# working.net
KiCad netlist of a schematic drawn in EAGLE
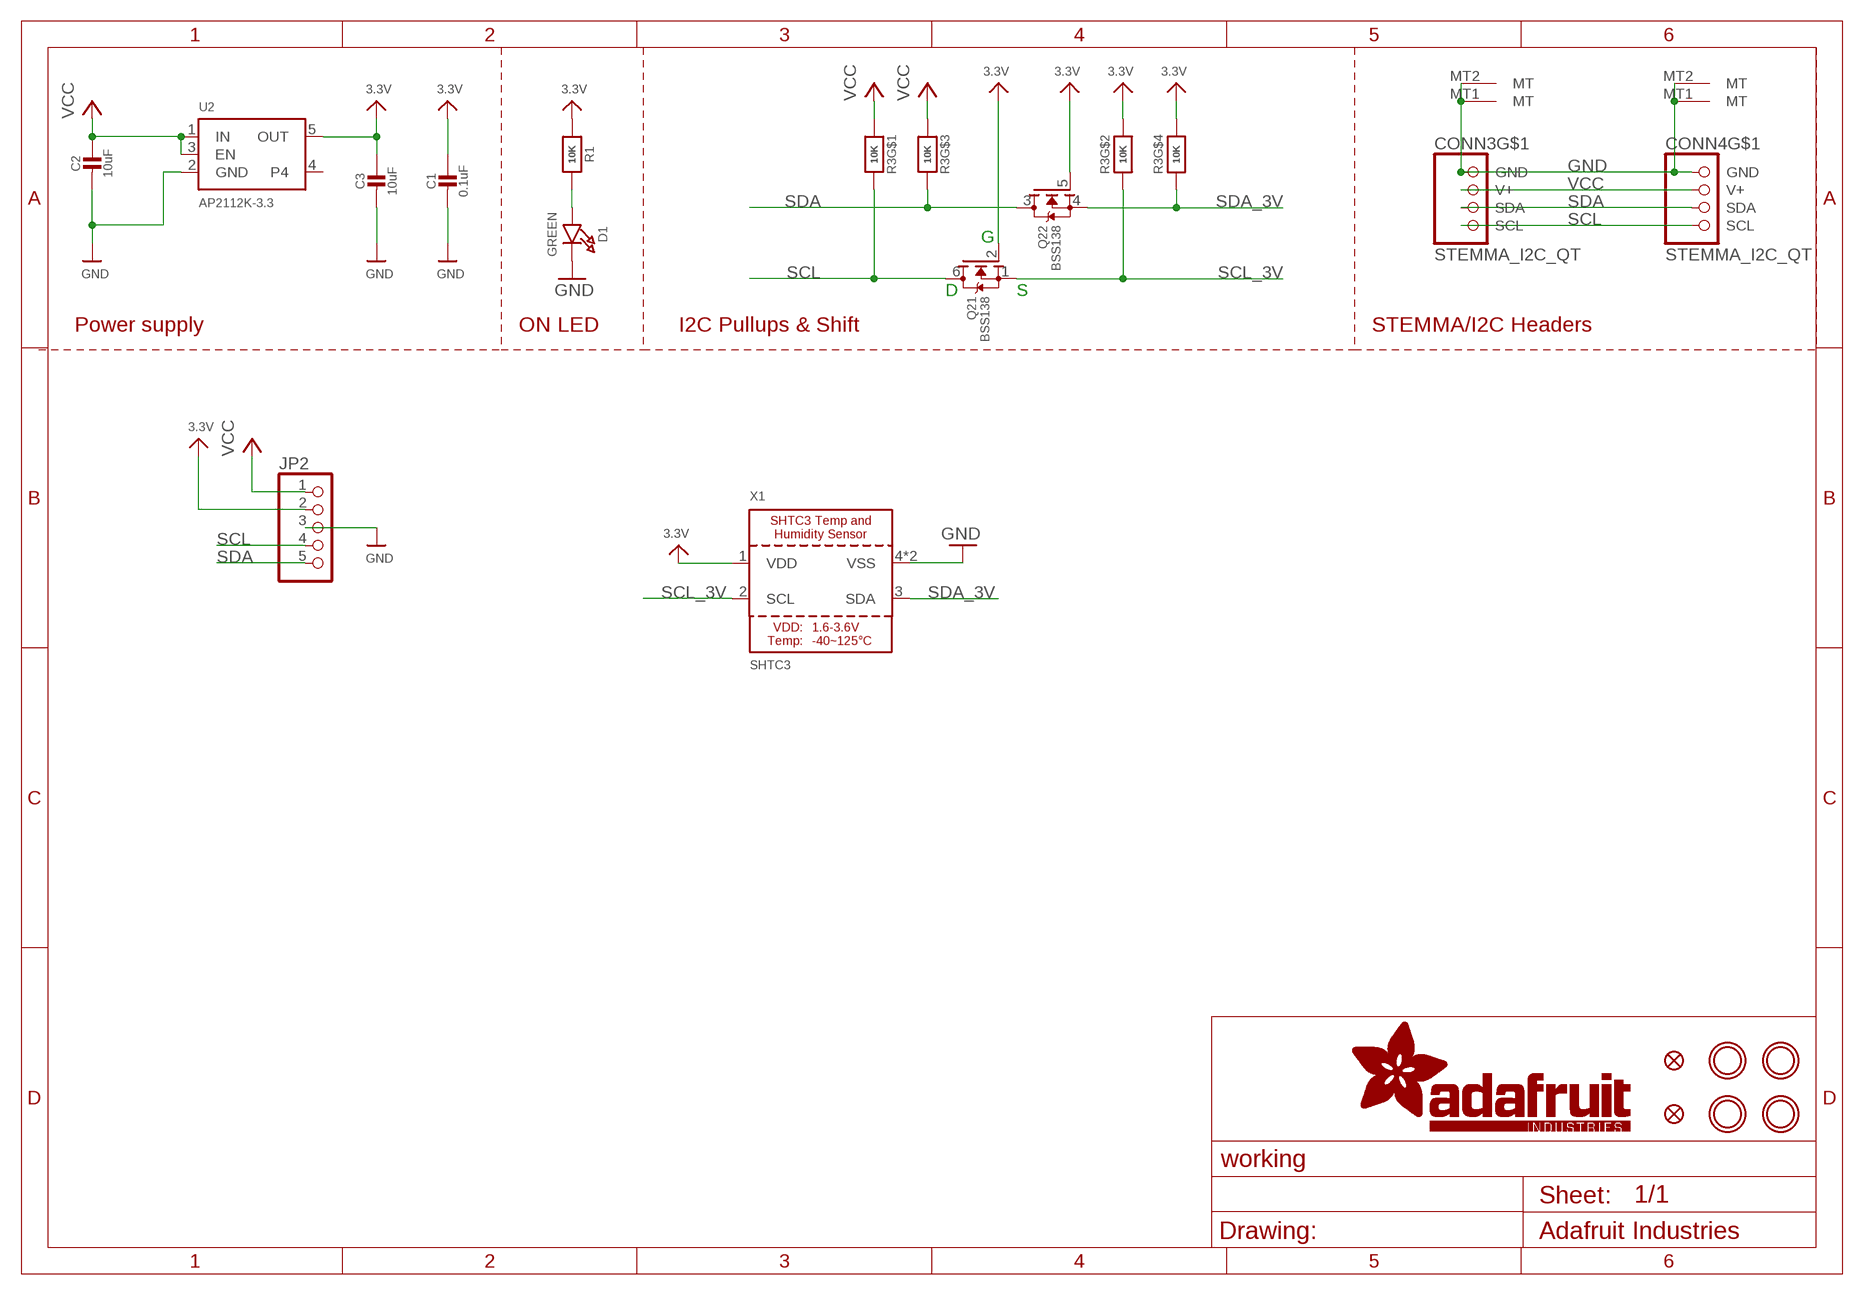
[diagram p0: schematic, sheet 1]

(export (version "E")
  (design (tool "Eeschema 10.0.6"))
  (components
    (comp (ref "C1")
      (value "0.1uF")
      (footprint "eagle-import:0603-NO")
      (libsource (lib "eagle-import") (part "CAP_CERAMIC0603_NO"))
    )
    (comp (ref "C2")
      (value "10uF")
      (footprint "eagle-import:0805-NO")
      (libsource (lib "eagle-import") (part "CAP_CERAMIC0805-NOOUTLINE"))
    )
    (comp (ref "C3")
      (value "10uF")
      (footprint "eagle-import:0805-NO")
      (libsource (lib "eagle-import") (part "CAP_CERAMIC0805-NOOUTLINE"))
    )
    (comp (ref "CONN3")
      (value "STEMMA_I2C_QT")
      (footprint "eagle-import:JST_SH4")
      (libsource (lib "eagle-import") (part "STEMMA_I2C_QT"))
    )
    (comp (ref "CONN4")
      (value "STEMMA_I2C_QT")
      (footprint "eagle-import:JST_SH4")
      (libsource (lib "eagle-import") (part "STEMMA_I2C_QT"))
    )
    (comp (ref "D1")
      (value "GREEN")
      (footprint "eagle-import:CHIPLED_0603_NOOUTLINE")
      (libsource (lib "eagle-import") (part "LED0603_NOOUTLINE"))
    )
    (comp (ref "FID3")
      (value "FIDUCIAL_1MM")
      (footprint "eagle-import:FIDUCIAL_1MM")
      (libsource (lib "eagle-import") (part "FIDUCIAL_1MM"))
    )
    (comp (ref "FID4")
      (value "FIDUCIAL_1MM")
      (footprint "eagle-import:FIDUCIAL_1MM")
      (libsource (lib "eagle-import") (part "FIDUCIAL_1MM"))
    )
    (comp (ref "JP2")
      (value "HEADER-1X570MIL")
      (footprint "eagle-import:1X05_ROUND_70")
      (libsource (lib "eagle-import") (part "HEADER-1X570MIL"))
    )
    (comp (ref "Q2")
      (value "BSS138")
      (footprint "eagle-import:SOT363")
      (libsource (lib "eagle-import") (part "MOSFET-N_DUAL"))
    )
    (comp (ref "R1")
      (value "10K")
      (footprint "eagle-import:0603-NO")
      (libsource (lib "eagle-import") (part "RESISTOR_0603_NOOUT"))
    )
    (comp (ref "R3")
      (value "10K")
      (footprint "eagle-import:RESPACK_4X0603")
      (libsource (lib "eagle-import") (part "RESISTOR_4PACK"))
    )
    (comp (ref "U$1")
      (value "MOUNTINGHOLE2.5")
      (footprint "eagle-import:MOUNTINGHOLE_2.5_PLATED")
      (libsource (lib "eagle-import") (part "MOUNTINGHOLE2.5"))
    )
    (comp (ref "U$17")
      (value "MOUNTINGHOLE2.5")
      (footprint "eagle-import:MOUNTINGHOLE_2.5_PLATED")
      (libsource (lib "eagle-import") (part "MOUNTINGHOLE2.5"))
    )
    (comp (ref "U$19")
      (value "MOUNTINGHOLE2.5")
      (footprint "eagle-import:MOUNTINGHOLE_2.5_PLATED")
      (libsource (lib "eagle-import") (part "MOUNTINGHOLE2.5"))
    )
    (comp (ref "U$21")
      (value "MOUNTINGHOLE2.5")
      (footprint "eagle-import:MOUNTINGHOLE_2.5_PLATED")
      (libsource (lib "eagle-import") (part "MOUNTINGHOLE2.5"))
    )
    (comp (ref "U2")
      (value "AP2112K-3.3")
      (footprint "eagle-import:SOT23-5")
      (libsource (lib "eagle-import") (part "VREG_SOT23-5"))
    )
    (comp (ref "X1")
      (value "SHTC3")
      (footprint "eagle-import:SHTC3")
      (libsource (lib "eagle-import") (part "SHTC3"))
    )
  )
  (nets
    (net (code "1") (name "/SCL") (class "Default")
      (node (ref "CONN3") (pin "4") (pinfunction "SCL_4") (pintype "passive"))
      (node (ref "CONN4") (pin "4") (pinfunction "SCL_4") (pintype "passive"))
      (node (ref "JP2") (pin "4") (pinfunction "4_4") (pintype "passive"))
      (node (ref "Q2") (pin "6") (pinfunction "D_6") (pintype "bidirectional"))
      (node (ref "R3") (pin "8") (pinfunction "2_8") (pintype "passive"))
    )
    (net (code "2") (name "/SCL_3V") (class "Default")
      (node (ref "Q2") (pin "1") (pinfunction "S_1") (pintype "bidirectional"))
      (node (ref "R3") (pin "7") (pinfunction "2_7") (pintype "passive"))
      (node (ref "X1") (pin "2") (pinfunction "SCL_2") (pintype "bidirectional"))
    )
    (net (code "3") (name "/SDA") (class "Default")
      (node (ref "CONN3") (pin "3") (pinfunction "SDA_3") (pintype "passive"))
      (node (ref "CONN4") (pin "3") (pinfunction "SDA_3") (pintype "passive"))
      (node (ref "JP2") (pin "5") (pinfunction "5_5") (pintype "passive"))
      (node (ref "Q2") (pin "3") (pinfunction "D_3") (pintype "bidirectional"))
      (node (ref "R3") (pin "6") (pinfunction "2_6") (pintype "passive"))
    )
    (net (code "4") (name "/SDA_3V") (class "Default")
      (node (ref "Q2") (pin "4") (pinfunction "S_4") (pintype "bidirectional"))
      (node (ref "R3") (pin "5") (pinfunction "2_5") (pintype "passive"))
      (node (ref "X1") (pin "3") (pinfunction "SDA_3") (pintype "bidirectional"))
    )
    (net (code "5") (name "3.3V") (class "Default")
      (node (ref "C1") (pin "1") (pinfunction "1_1") (pintype "passive"))
      (node (ref "C3") (pin "1") (pinfunction "1_1") (pintype "passive"))
      (node (ref "JP2") (pin "2") (pinfunction "2_2") (pintype "passive"))
      (node (ref "Q2") (pin "2") (pinfunction "G_2") (pintype "bidirectional"))
      (node (ref "Q2") (pin "5") (pinfunction "G_5") (pintype "bidirectional"))
      (node (ref "R1") (pin "1") (pinfunction "1_1") (pintype "passive"))
      (node (ref "R3") (pin "2") (pinfunction "1_2") (pintype "passive"))
      (node (ref "R3") (pin "4") (pinfunction "1_4") (pintype "passive"))
      (node (ref "U2") (pin "5") (pinfunction "OUT_5") (pintype "power_in"))
      (node (ref "X1") (pin "1") (pinfunction "VDD_1") (pintype "power_in"))
    )
    (net (code "6") (name "GND") (class "Default")
      (node (ref "C1") (pin "2") (pinfunction "2_2") (pintype "passive"))
      (node (ref "C2") (pin "2") (pinfunction "2_2") (pintype "passive"))
      (node (ref "C3") (pin "2") (pinfunction "2_2") (pintype "passive"))
      (node (ref "CONN3") (pin "1") (pinfunction "GND_1") (pintype "passive"))
      (node (ref "CONN3") (pin "MT1") (pinfunction "MT_MT1") (pintype "bidirectional"))
      (node (ref "CONN3") (pin "MT2") (pinfunction "MT_MT2") (pintype "bidirectional"))
      (node (ref "CONN4") (pin "1") (pinfunction "GND_1") (pintype "passive"))
      (node (ref "CONN4") (pin "MT1") (pinfunction "MT_MT1") (pintype "bidirectional"))
      (node (ref "CONN4") (pin "MT2") (pinfunction "MT_MT2") (pintype "bidirectional"))
      (node (ref "D1") (pin "C") (pinfunction "C_C") (pintype "passive"))
      (node (ref "JP2") (pin "3") (pinfunction "3_3") (pintype "passive"))
      (node (ref "U2") (pin "2") (pinfunction "GND_2") (pintype "power_in"))
      (node (ref "X1") (pin "4") (pinfunction "VSS_4") (pintype "power_in"))
      (node (ref "X1") (pin "MNT") (pinfunction "VSS_MNT") (pintype "power_in"))
    )
    (net (code "7") (name "Net-(D1-PadA)") (class "Default")
      (node (ref "D1") (pin "A") (pinfunction "A_A") (pintype "passive"))
      (node (ref "R1") (pin "2") (pinfunction "2_2") (pintype "passive"))
    )
    (net (code "8") (name "VCC") (class "Default")
      (node (ref "C2") (pin "1") (pinfunction "1_1") (pintype "passive"))
      (node (ref "CONN3") (pin "2") (pinfunction "V+_2") (pintype "passive"))
      (node (ref "CONN4") (pin "2") (pinfunction "V+_2") (pintype "passive"))
      (node (ref "JP2") (pin "1") (pinfunction "1_1") (pintype "passive"))
      (node (ref "R3") (pin "1") (pinfunction "1_1") (pintype "passive"))
      (node (ref "R3") (pin "3") (pinfunction "1_3") (pintype "passive"))
      (node (ref "U2") (pin "1") (pinfunction "IN_1") (pintype "power_in"))
      (node (ref "U2") (pin "3") (pinfunction "EN_3") (pintype "input"))
    )
    (net (code "9") (name "unconnected-(U2-P4-Pad4)") (class "Default")
      (node (ref "U2") (pin "4") (pinfunction "P4_4") (pintype "bidirectional"))
    )
  )
)
